# CPS.net
KiCad netlist of a schematic drawn in Altium Designer
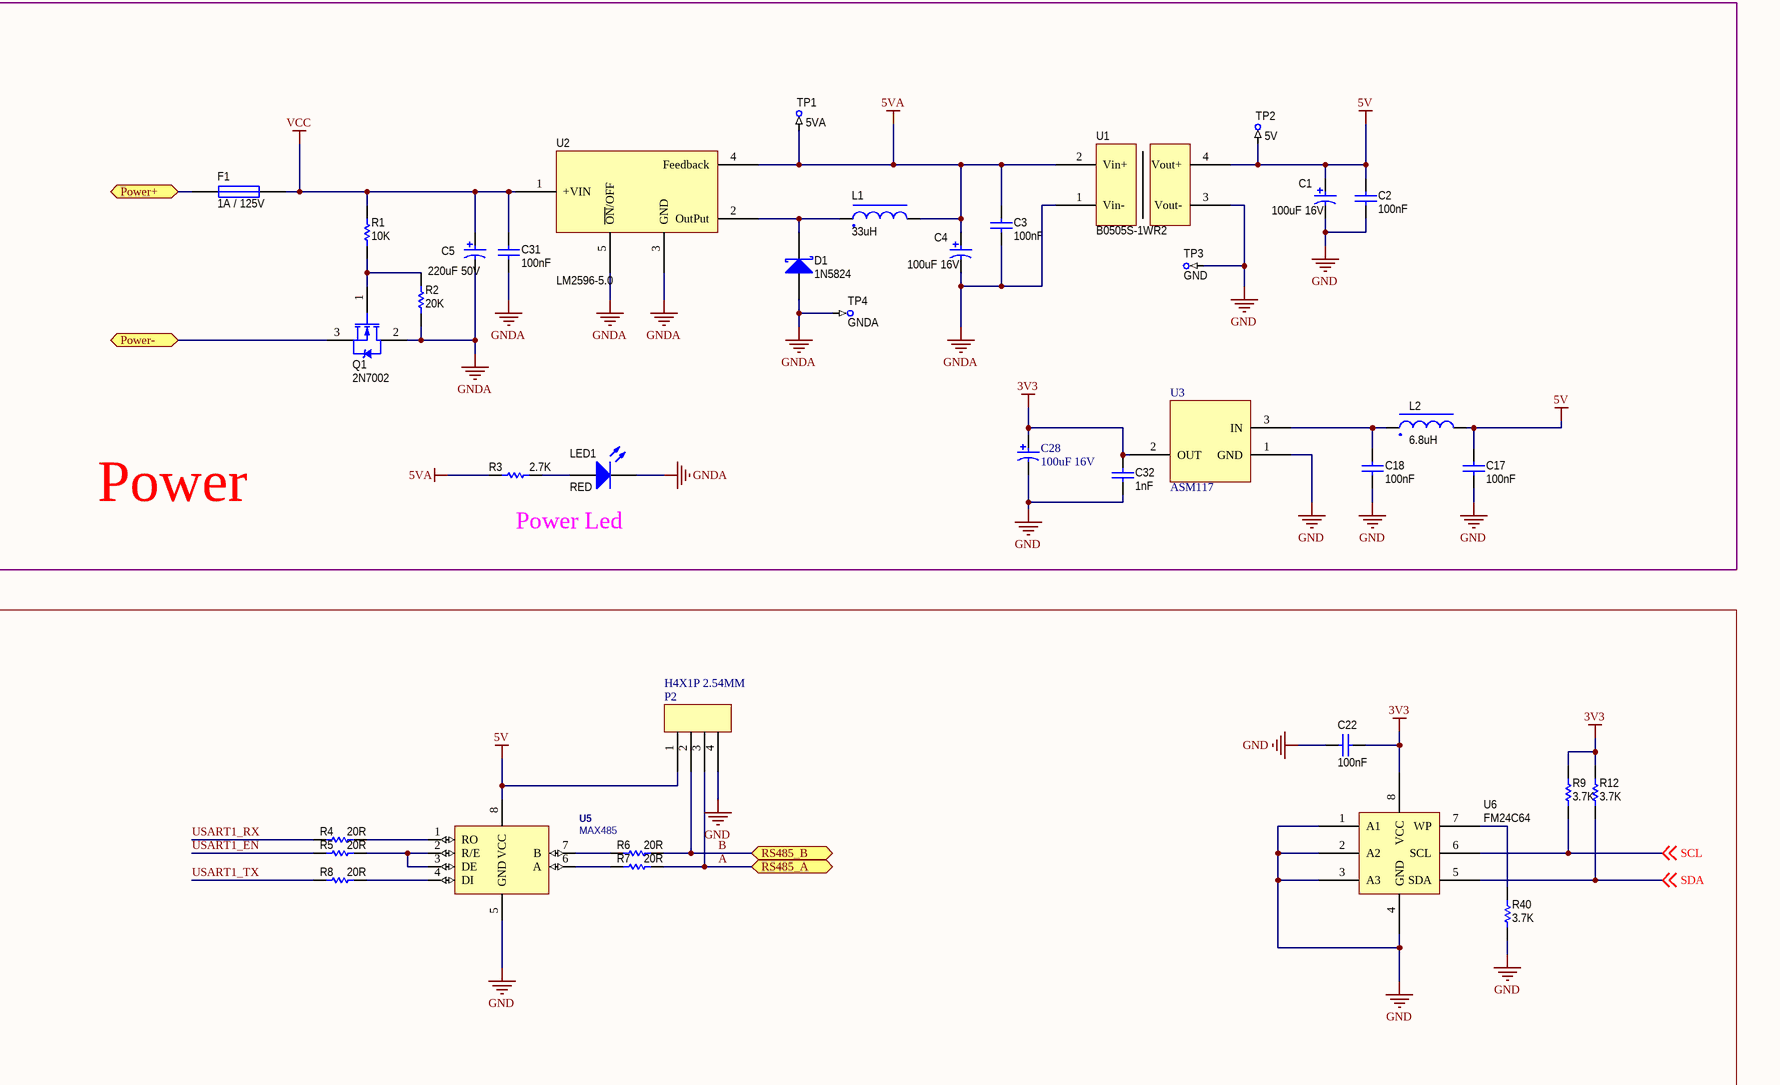
[diagram p0: CPS.SchDoc, top left]
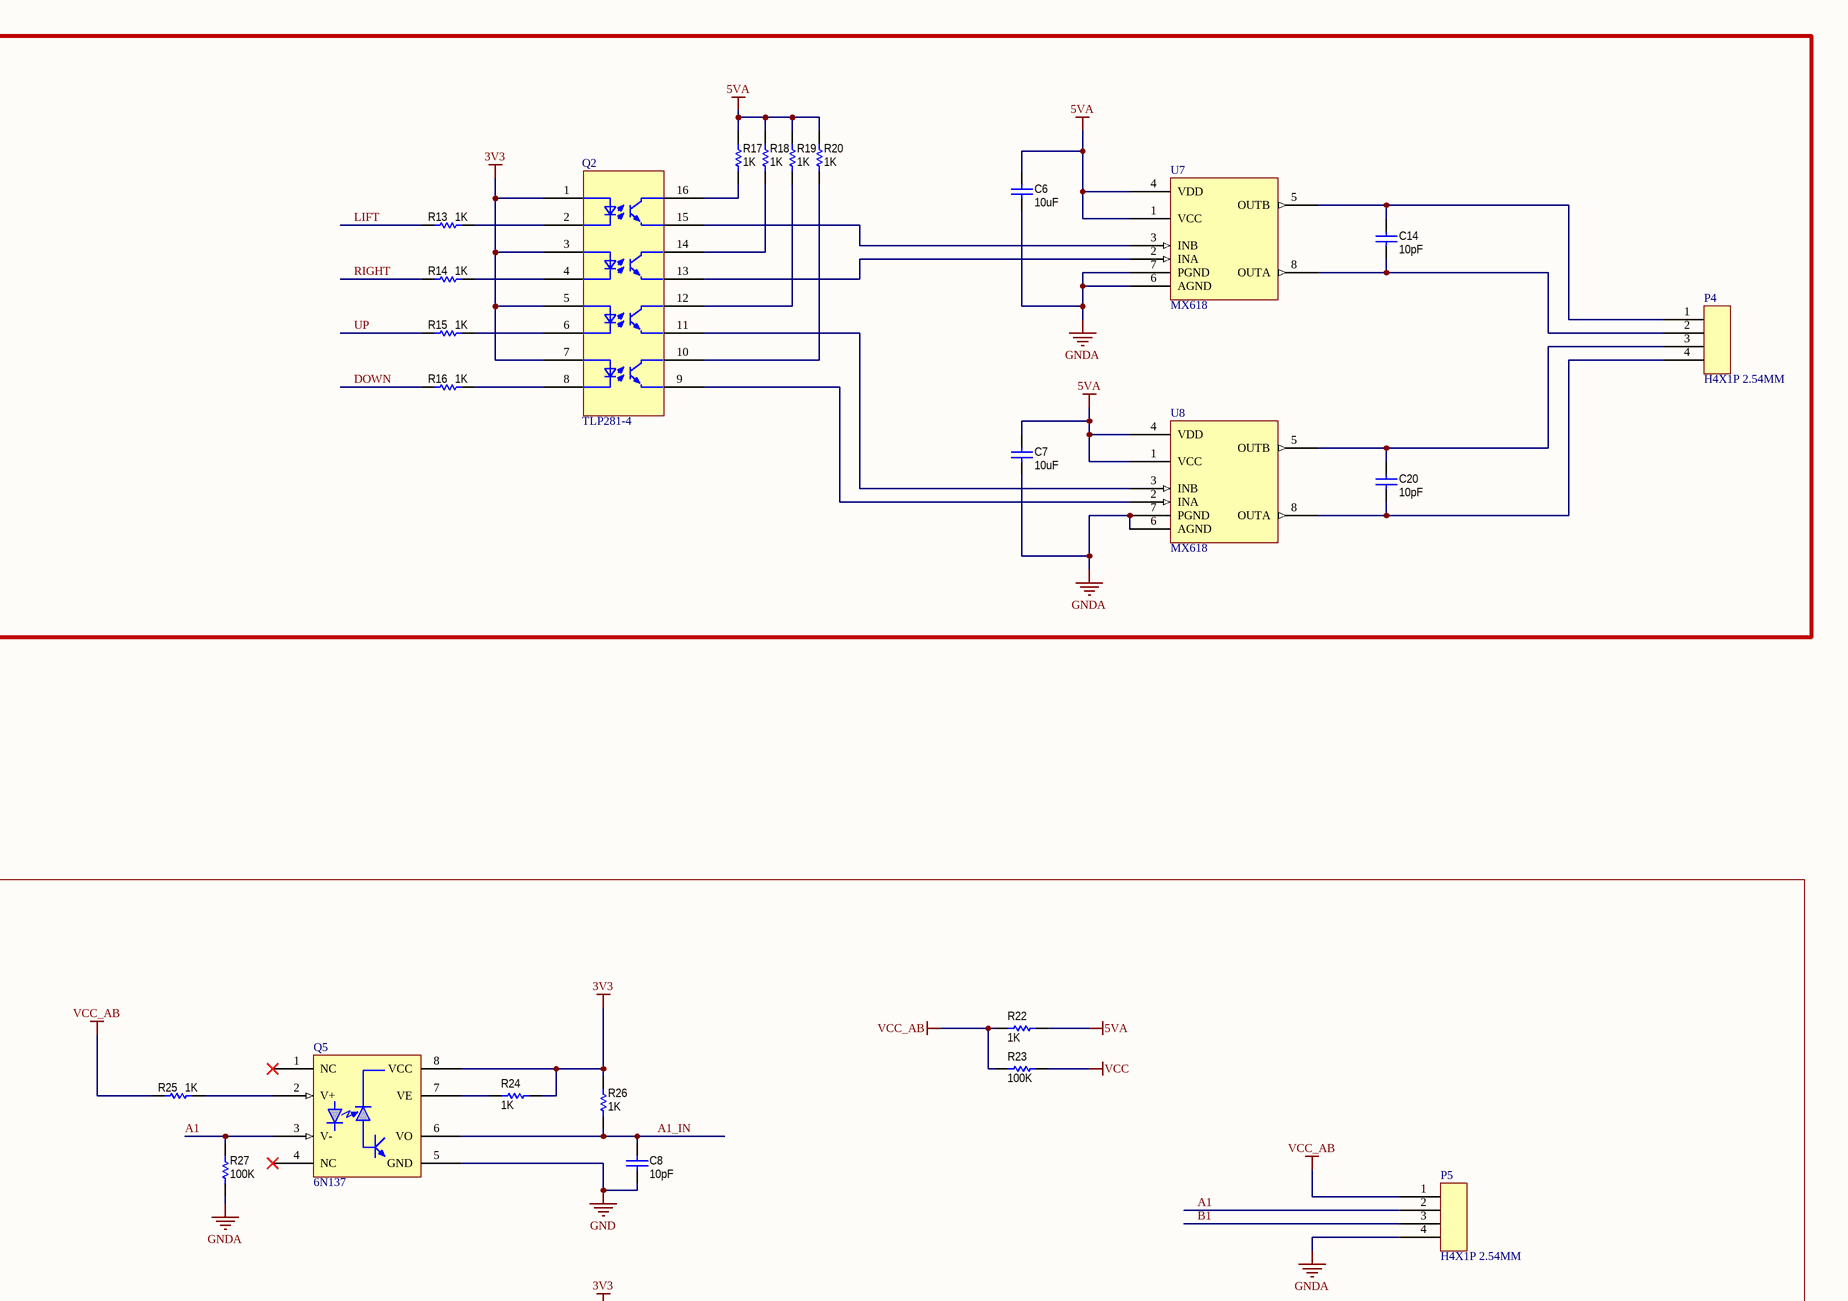
[diagram p1: CPS.SchDoc, top right]
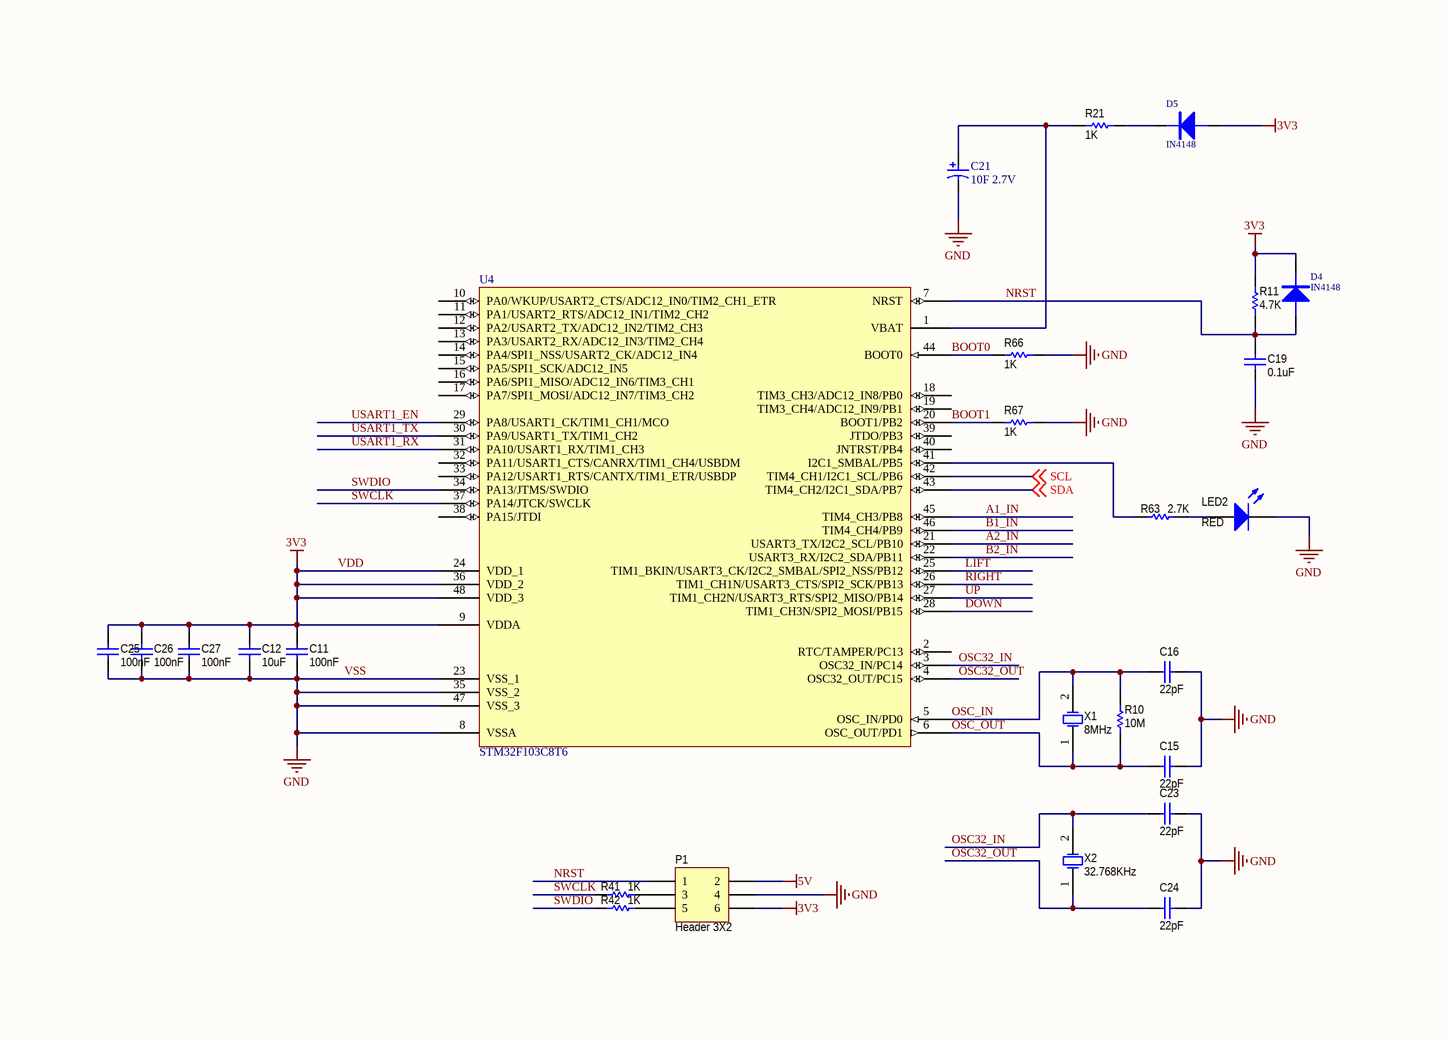
[diagram p2: CPS.SchDoc, bottom left]
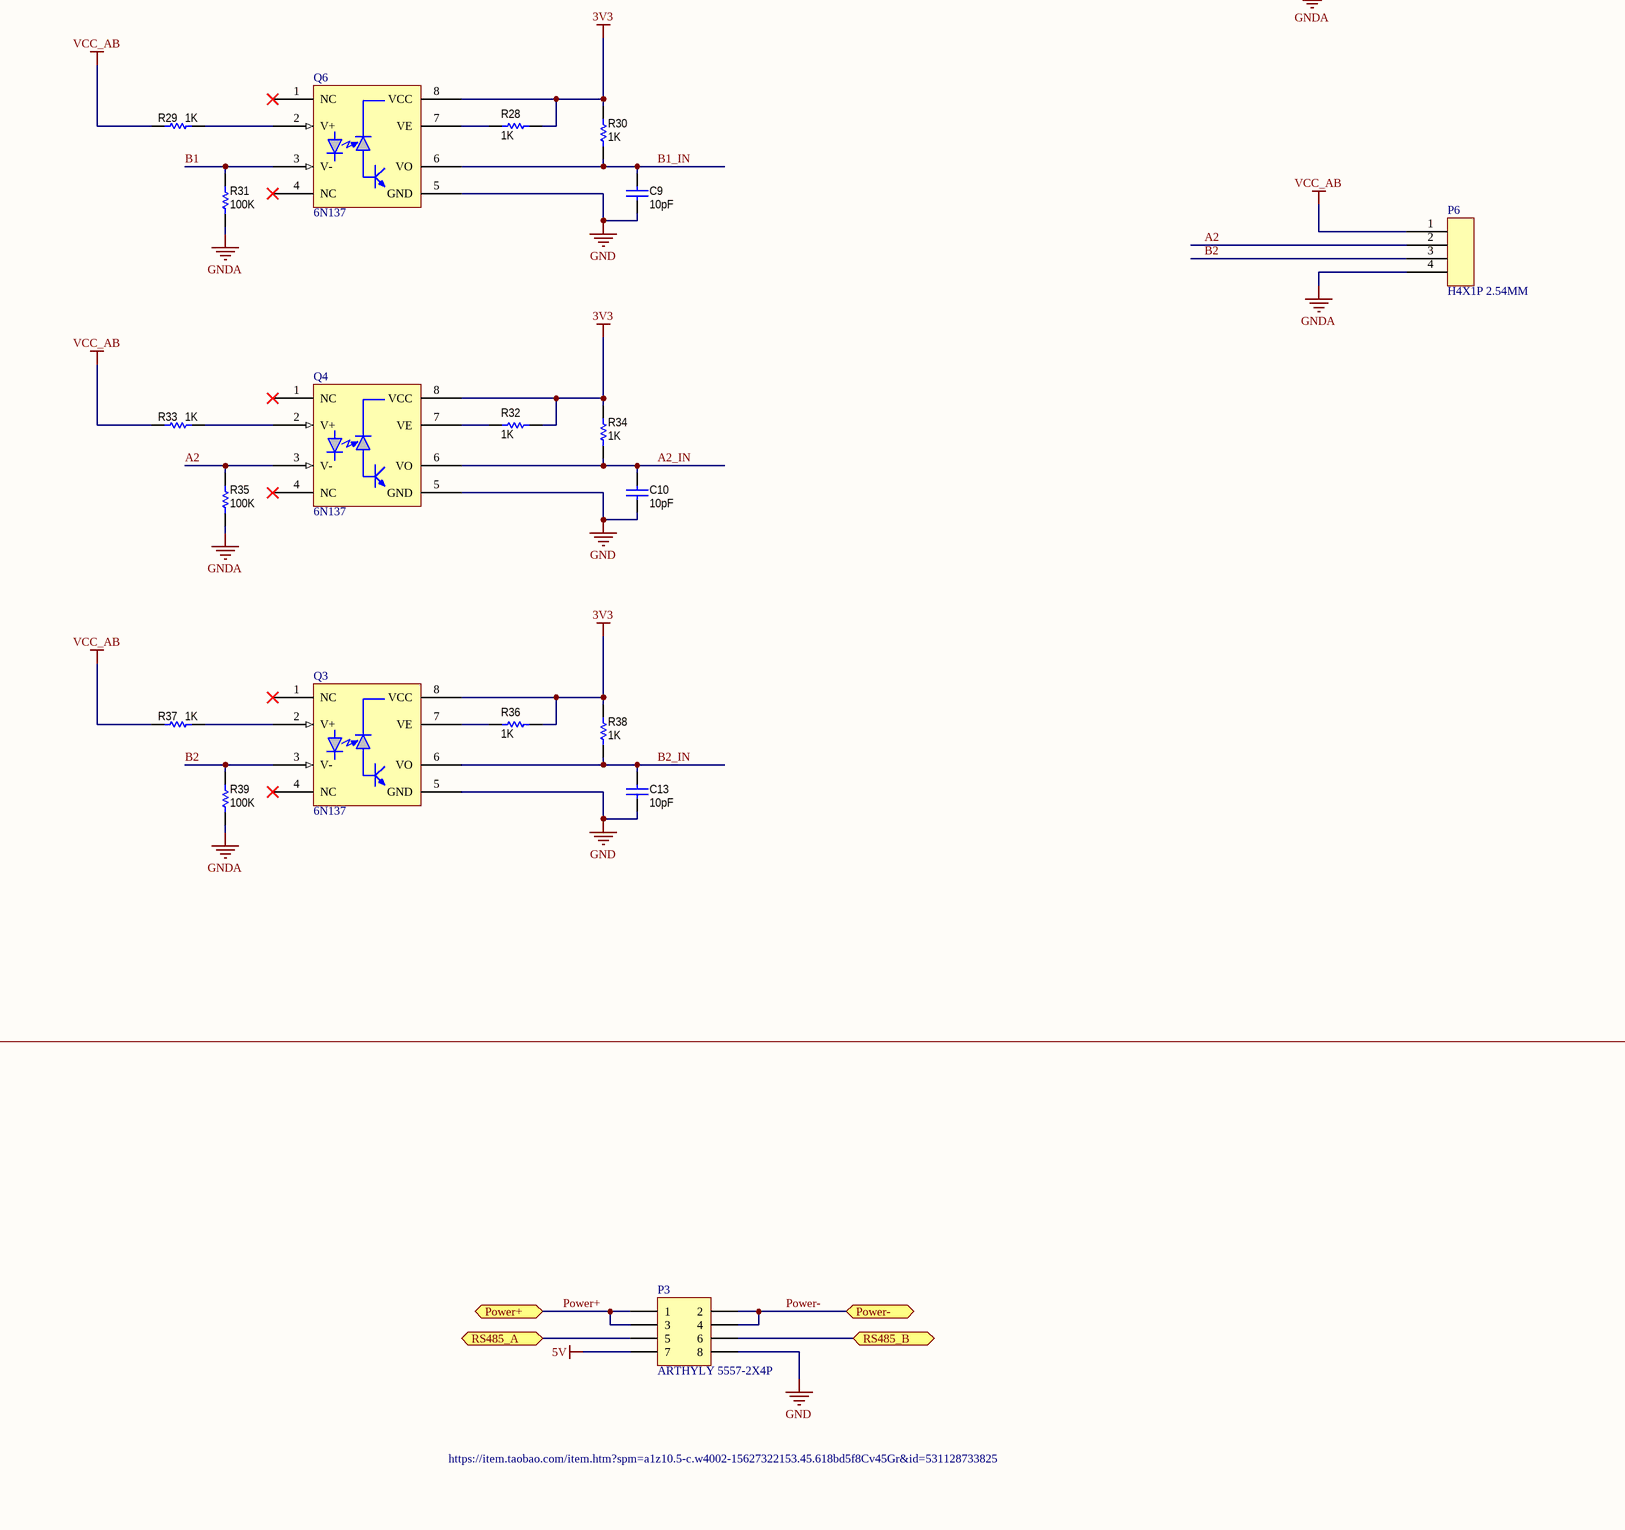
[diagram p3: CPS.SchDoc, bottom right]

(export (version "E")
  (design (tool "Eeschema 10.0.6"))
  (components
    (comp (ref "C1")
      (value "100uF 16V")
      (footprint "SMD-D6.5MM")
      (description "Polar Capacitor")
      (libsource (lib "ZLM") (part "CAP-P"))
    )
    (comp (ref "C2")
      (value "100nF")
      (footprint "0603S")
      (description "Capacitor")
      (libsource (lib "ZLM") (part "CAP-NP"))
    )
    (comp (ref "C3")
      (value "100nF")
      (footprint "0603S")
      (description "Capacitor")
      (libsource (lib "ZLM") (part "CAP-NP"))
    )
    (comp (ref "C4")
      (value "100uF 16V")
      (footprint "SMD-D6.5MM")
      (description "Polar Capacitor")
      (libsource (lib "ZLM") (part "CAP-P"))
    )
    (comp (ref "C5")
      (value "220uF 50V")
      (footprint "SMD-D10MM")
      (description "Polar Capacitor")
      (libsource (lib "ZLM") (part "CAP-P"))
    )
    (comp (ref "C6")
      (value "10uF")
      (footprint "1210S")
      (description "Capacitor")
      (libsource (lib "ZLM") (part "CAP-NP"))
    )
    (comp (ref "C7")
      (value "10uF")
      (footprint "1210S")
      (description "Capacitor")
      (libsource (lib "ZLM") (part "CAP-NP"))
    )
    (comp (ref "C8")
      (value "10pF")
      (footprint "0805S")
      (description "Capacitor")
      (libsource (lib "ZLM") (part "CAP-NP"))
    )
    (comp (ref "C9")
      (value "10pF")
      (footprint "0805S")
      (description "Capacitor")
      (libsource (lib "ZLM") (part "CAP-NP"))
    )
    (comp (ref "C10")
      (value "10pF")
      (footprint "0805S")
      (description "Capacitor")
      (libsource (lib "ZLM") (part "CAP-NP"))
    )
    (comp (ref "C11")
      (value "100nF")
      (footprint "0603S")
      (description "Capacitor")
      (libsource (lib "ZLM") (part "CAP-NP"))
    )
    (comp (ref "C12")
      (value "10uF")
      (footprint "1210S")
      (description "Capacitor")
      (libsource (lib "ZLM") (part "CAP-NP"))
    )
    (comp (ref "C13")
      (value "10pF")
      (footprint "0805S")
      (description "Capacitor")
      (libsource (lib "ZLM") (part "CAP-NP"))
    )
    (comp (ref "C14")
      (value "10pF")
      (footprint "0805S")
      (description "Capacitor")
      (libsource (lib "ZLM") (part "CAP-NP"))
    )
    (comp (ref "C15")
      (value "22pF")
      (footprint "0603S")
      (description "Capacitor")
      (libsource (lib "ZLM") (part "CAP-NP"))
    )
    (comp (ref "C16")
      (value "22pF")
      (footprint "0603S")
      (description "Capacitor")
      (libsource (lib "ZLM") (part "CAP-NP"))
    )
    (comp (ref "C17")
      (value "100nF")
      (footprint "0805S")
      (description "Capacitor")
      (libsource (lib "ZLM") (part "CAP-NP"))
    )
    (comp (ref "C18")
      (value "100nF")
      (footprint "0805S")
      (description "Capacitor")
      (libsource (lib "ZLM") (part "CAP-NP"))
    )
    (comp (ref "C19")
      (value "0.1uF")
      (footprint "0603S")
      (description "Capacitor")
      (libsource (lib "ZLM") (part "CAP-NP"))
    )
    (comp (ref "C20")
      (value "10pF")
      (footprint "0805S")
      (description "Capacitor")
      (libsource (lib "ZLM") (part "CAP-NP"))
    )
    (comp (ref "C21")
      (value "10F 2.7V")
      (footprint "DIP2_90_31MM")
      (description "Polar Capacitor")
      (libsource (lib "ZLM") (part "CAP-P"))
    )
    (comp (ref "C22")
      (value "100nF")
      (footprint "0805S")
      (description "Capacitor")
      (libsource (lib "ZLM") (part "CAP-NP"))
    )
    (comp (ref "C23")
      (value "22pF")
      (footprint "0603S")
      (description "Capacitor")
      (libsource (lib "ZLM") (part "CAP-NP"))
    )
    (comp (ref "C24")
      (value "22pF")
      (footprint "0603S")
      (description "Capacitor")
      (libsource (lib "ZLM") (part "CAP-NP"))
    )
    (comp (ref "C25")
      (value "100nF")
      (footprint "0603S")
      (description "Capacitor")
      (libsource (lib "ZLM") (part "CAP-NP"))
    )
    (comp (ref "C26")
      (value "100nF")
      (footprint "0603S")
      (description "Capacitor")
      (libsource (lib "ZLM") (part "CAP-NP"))
    )
    (comp (ref "C27")
      (value "100nF")
      (footprint "0603S")
      (description "Capacitor")
      (libsource (lib "ZLM") (part "CAP-NP"))
    )
    (comp (ref "C28")
      (value "100uF 16V")
      (footprint "SMD-D6.5MM")
      (description "Polar Capacitor")
      (libsource (lib "ZLM") (part "CAP-P"))
    )
    (comp (ref "C31")
      (value "100nF")
      (footprint "0805S")
      (description "Capacitor")
      (libsource (lib "ZLM") (part "CAP-NP"))
    )
    (comp (ref "C32")
      (value "1nF")
      (footprint "0603S")
      (description "Capacitor")
      (libsource (lib "ZLM") (part "CAP-NP"))
    )
    (comp (ref "D1")
      (value "1N5824")
      (footprint "DO-214AC")
      (description "Schottky Barrier Double Diode")
      (libsource (lib "ZLM") (part "DIO-SCHOTTKY-1S-SOT23"))
    )
    (comp (ref "D4")
      (value "IN4148")
      (footprint "1206D")
      (description "Silicon Epitaxial Planar Switching Diode,75V")
      (libsource (lib "ZLM") (part "DIO_SWITCH"))
    )
    (comp (ref "D5")
      (value "IN4148")
      (footprint "1206D")
      (description "Silicon Epitaxial Planar Switching Diode,75V")
      (libsource (lib "ZLM") (part "DIO_SWITCH"))
    )
    (comp (ref "F1")
      (value "1A / 125V")
      (footprint "1810S")
      (description "Fuse")
      (fields (field (name "PUBLISHER") "Altium Limited"))
      (libsource (lib "Miscellaneous Devices") (part "Fuse 1"))
    )
    (comp (ref "L1")
      (value "33uH")
      (footprint "SMD12X12X7")
      (description "Inductor_1")
      (libsource (lib "ZLM") (part "Inductor_1"))
    )
    (comp (ref "L2")
      (value "6.8uH")
      (footprint "0805S")
      (description "Inductor_1")
      (libsource (lib "ZLM") (part "Inductor_1"))
    )
    (comp (ref "LED1")
      (value "RED")
      (footprint "0805SN")
      (description "Typical GREEN SMD LED Agilent make")
      (libsource (lib "ZLM") (part "DIO-LED-1S"))
    )
    (comp (ref "LED2")
      (value "RED")
      (footprint "0805SN")
      (description "Typical GREEN SMD LED Agilent make")
      (libsource (lib "ZLM") (part "DIO-LED-1S"))
    )
    (comp (ref "P1")
      (value "Header 3X2")
      (footprint "Header3x2")
      (description "Header, 3-Pin, Dual row")
      (fields (field (name "PUBLISHER") "Altium Limited"))
      (libsource (lib "Miscellaneous Connectors") (part "Header 3X2"))
    )
    (comp (ref "P2")
      (value "H4X1P 2.54MM")
      (footprint "HDR1X4H-2.54MM")
      (libsource (lib "") (part "H4X1P_1"))
    )
    (comp (ref "P3")
      (value "ARTHYLY 5557-2X4P")
      (footprint "5557_2X4P")
      (description "Header, 4-Pin, Dual row")
      (fields (field (name "PUBLISHER") "Altium Limited"))
      (libsource (lib "Miscellaneous Connectors") (part "Header 4X2"))
    )
    (comp (ref "P4")
      (value "H4X1P 2.54MM")
      (footprint "HDR1X4H-2.54MM")
      (libsource (lib "ZLM") (part "H4X1P"))
    )
    (comp (ref "P5")
      (value "H4X1P 2.54MM")
      (footprint "HDR1X4H-2.54MM")
      (libsource (lib "ZLM") (part "H4X1P"))
    )
    (comp (ref "P6")
      (value "H4X1P 2.54MM")
      (footprint "HDR1X4H-2.54MM")
      (libsource (lib "ZLM") (part "H4X1P"))
    )
    (comp (ref "Q1")
      (value "2N7002")
      (footprint "TO-253")
      (description "N-Channel MOSFET")
      (libsource (lib "ZLM") (part "NMOS"))
    )
    (comp (ref "Q2")
      (value "TLP281-4")
      (footprint "SOP-16")
      (description "TLP281-4 TOSHIBA PHOTOCOUPLER GaAs IRED & PHOTO-TRANSISTOR")
      (libsource (lib "ZLM") (part "Optocoupler 4Pass"))
    )
    (comp (ref "Q3") (value "6N137") (footprint "DIP8") (libsource (lib "ZLM") (part "6N137")))
    (comp (ref "Q4") (value "6N137") (footprint "DIP8") (libsource (lib "ZLM") (part "6N137")))
    (comp (ref "Q5") (value "6N137") (footprint "DIP8") (libsource (lib "ZLM") (part "6N137")))
    (comp (ref "Q6") (value "6N137") (footprint "DIP8") (libsource (lib "ZLM") (part "6N137")))
    (comp (ref "R1")
      (value "10K")
      (footprint "0603S")
      (description "Resistor")
      (libsource (lib "ZLM") (part "RES"))
    )
    (comp (ref "R2")
      (value "20K")
      (footprint "0603S")
      (description "Resistor")
      (libsource (lib "ZLM") (part "RES"))
    )
    (comp (ref "R3")
      (value "2.7K")
      (footprint "0603S")
      (description "Resistor")
      (libsource (lib "ZLM") (part "RES"))
    )
    (comp (ref "R4")
      (value "20R")
      (footprint "0603S")
      (description "Resistor")
      (libsource (lib "ZLM") (part "RES"))
    )
    (comp (ref "R5")
      (value "20R")
      (footprint "0603S")
      (description "Resistor")
      (libsource (lib "ZLM") (part "RES"))
    )
    (comp (ref "R6")
      (value "20R")
      (footprint "0603S")
      (description "Resistor")
      (libsource (lib "ZLM") (part "RES"))
    )
    (comp (ref "R7")
      (value "20R")
      (footprint "0603S")
      (description "Resistor")
      (libsource (lib "ZLM") (part "RES"))
    )
    (comp (ref "R8")
      (value "20R")
      (footprint "0603S")
      (description "Resistor")
      (libsource (lib "ZLM") (part "RES"))
    )
    (comp (ref "R9")
      (value "3.7K")
      (footprint "0603S")
      (description "Resistor")
      (libsource (lib "ZLM") (part "RES"))
    )
    (comp (ref "R10")
      (value "10M")
      (footprint "0603S")
      (description "Resistor")
      (libsource (lib "ZLM") (part "RES"))
    )
    (comp (ref "R11")
      (value "4.7K")
      (footprint "0603S")
      (description "Resistor")
      (libsource (lib "ZLM") (part "RES"))
    )
    (comp (ref "R12")
      (value "3.7K")
      (footprint "0603S")
      (description "Resistor")
      (libsource (lib "ZLM") (part "RES"))
    )
    (comp (ref "R13")
      (value "1K")
      (footprint "0603S")
      (description "Resistor")
      (libsource (lib "ZLM") (part "RES"))
    )
    (comp (ref "R14")
      (value "1K")
      (footprint "0603S")
      (description "Resistor")
      (libsource (lib "ZLM") (part "RES"))
    )
    (comp (ref "R15")
      (value "1K")
      (footprint "0603S")
      (description "Resistor")
      (libsource (lib "ZLM") (part "RES"))
    )
    (comp (ref "R16")
      (value "1K")
      (footprint "0603S")
      (description "Resistor")
      (libsource (lib "ZLM") (part "RES"))
    )
    (comp (ref "R17")
      (value "1K")
      (footprint "0603S")
      (description "Resistor")
      (libsource (lib "ZLM") (part "RES"))
    )
    (comp (ref "R18")
      (value "1K")
      (footprint "0603S")
      (description "Resistor")
      (libsource (lib "ZLM") (part "RES"))
    )
    (comp (ref "R19")
      (value "1K")
      (footprint "0603S")
      (description "Resistor")
      (libsource (lib "ZLM") (part "RES"))
    )
    (comp (ref "R20")
      (value "1K")
      (footprint "0603S")
      (description "Resistor")
      (libsource (lib "ZLM") (part "RES"))
    )
    (comp (ref "R21")
      (value "1K")
      (footprint "1206R")
      (description "Resistor")
      (libsource (lib "ZLM") (part "RES"))
    )
    (comp (ref "R22")
      (value "1K")
      (footprint "1206R")
      (description "Resistor")
      (libsource (lib "ZLM") (part "RES"))
    )
    (comp (ref "R23")
      (value "100K")
      (footprint "1206R")
      (description "Resistor")
      (libsource (lib "ZLM") (part "RES"))
    )
    (comp (ref "R24")
      (value "1K")
      (footprint "0603S")
      (description "Resistor")
      (libsource (lib "ZLM") (part "RES"))
    )
    (comp (ref "R25")
      (value "1K")
      (footprint "0603S")
      (description "Resistor")
      (libsource (lib "ZLM") (part "RES"))
    )
    (comp (ref "R26")
      (value "1K")
      (footprint "0603S")
      (description "Resistor")
      (libsource (lib "ZLM") (part "RES"))
    )
    (comp (ref "R27")
      (value "100K")
      (footprint "0603S")
      (description "Resistor")
      (libsource (lib "ZLM") (part "RES"))
    )
    (comp (ref "R28")
      (value "1K")
      (footprint "0603S")
      (description "Resistor")
      (libsource (lib "ZLM") (part "RES"))
    )
    (comp (ref "R29")
      (value "1K")
      (footprint "0603S")
      (description "Resistor")
      (libsource (lib "ZLM") (part "RES"))
    )
    (comp (ref "R30")
      (value "1K")
      (footprint "0603S")
      (description "Resistor")
      (libsource (lib "ZLM") (part "RES"))
    )
    (comp (ref "R31")
      (value "100K")
      (footprint "0603S")
      (description "Resistor")
      (libsource (lib "ZLM") (part "RES"))
    )
    (comp (ref "R32")
      (value "1K")
      (footprint "0603S")
      (description "Resistor")
      (libsource (lib "ZLM") (part "RES"))
    )
    (comp (ref "R33")
      (value "1K")
      (footprint "0603S")
      (description "Resistor")
      (libsource (lib "ZLM") (part "RES"))
    )
    (comp (ref "R34")
      (value "1K")
      (footprint "0603S")
      (description "Resistor")
      (libsource (lib "ZLM") (part "RES"))
    )
    (comp (ref "R35")
      (value "100K")
      (footprint "0603S")
      (description "Resistor")
      (libsource (lib "ZLM") (part "RES"))
    )
    (comp (ref "R36")
      (value "1K")
      (footprint "0603S")
      (description "Resistor")
      (libsource (lib "ZLM") (part "RES"))
    )
    (comp (ref "R37")
      (value "1K")
      (footprint "0603S")
      (description "Resistor")
      (libsource (lib "ZLM") (part "RES"))
    )
    (comp (ref "R38")
      (value "1K")
      (footprint "0603S")
      (description "Resistor")
      (libsource (lib "ZLM") (part "RES"))
    )
    (comp (ref "R39")
      (value "100K")
      (footprint "0603S")
      (description "Resistor")
      (libsource (lib "ZLM") (part "RES"))
    )
    (comp (ref "R40")
      (value "3.7K")
      (footprint "0603S")
      (description "Resistor")
      (libsource (lib "ZLM") (part "RES"))
    )
    (comp (ref "R41")
      (value "1K")
      (footprint "0603S")
      (description "Resistor")
      (libsource (lib "ZLM") (part "RES"))
    )
    (comp (ref "R42")
      (value "1K")
      (footprint "0603S")
      (description "Resistor")
      (libsource (lib "ZLM") (part "RES"))
    )
    (comp (ref "R63")
      (value "2.7K")
      (footprint "0603S")
      (description "Resistor")
      (libsource (lib "ZLM") (part "RES"))
    )
    (comp (ref "R66")
      (value "1K")
      (footprint "0603S")
      (description "Resistor")
      (libsource (lib "ZLM") (part "RES"))
    )
    (comp (ref "R67")
      (value "1K")
      (footprint "0603S")
      (description "Resistor")
      (libsource (lib "ZLM") (part "RES"))
    )
    (comp (ref "TP1") (value "5VA") (footprint "T60") (libsource (lib "ZLM") (part "TestPin")))
    (comp (ref "TP2") (value "5V") (footprint "T60") (libsource (lib "ZLM") (part "TestPin")))
    (comp (ref "TP3") (value "GND") (footprint "T60") (libsource (lib "ZLM") (part "TestPin")))
    (comp (ref "TP4") (value "GNDA") (footprint "T60") (libsource (lib "ZLM") (part "TestPin")))
    (comp (ref "U1")
      (value "B0505S-1WR2")
      (footprint "DC/DC 2.54-4P")
      (description "MORNSUN DC/DC")
      (libsource (lib "ZLM") (part "DC/DC"))
    )
    (comp (ref "U2")
      (value "LM2596-5.0")
      (footprint "SOT-263-5")
      (description "LM2596 SIMPLE SWITCHER? Power Converter 150-kHz  3-A Step-Down Voltage Regulator")
      (libsource (lib "ZLM") (part "LM2596-5.0"))
    )
    (comp (ref "U3") (value "ASM117") (footprint "SOT-223") (libsource (lib "ASM117") (part "ASM117")))
    (comp (ref "U4")
      (value "STM32F103C8T6")
      (footprint "LQFP-48")
      (description "ST MCU,STM32F103C8T6,64Kb Flash,20Kb RAM")
      (libsource (lib "ZLM") (part "STM32F103C8T6"))
    )
    (comp (ref "U5")
      (value "MAX485")
      (footprint "SOP-8")
      (description "MAXIM,RS-485/RS-422 Transceivers")
      (libsource (lib "ZLM") (part "RS485"))
    )
    (comp (ref "U6")
      (value "FM24C64")
      (footprint "SOP-8")
      (description "FM24C64,8K FLASH,IIC")
      (libsource (lib "ZLM") (part "F24CXX"))
    )
    (comp (ref "U7")
      (value "MX618")
      (footprint "SOP-8")
      (description "DC 2V-9.6V Motor Contl")
      (libsource (lib "ZLM") (part "MX618"))
    )
    (comp (ref "U8")
      (value "MX618")
      (footprint "SOP-8")
      (description "DC 2V-9.6V Motor Contl")
      (libsource (lib "ZLM") (part "MX618"))
    )
    (comp (ref "X1")
      (value "8MHz")
      (footprint "5032")
      (description "Crystal Oscillator")
      (fields (field (name "PUBLISHER") "Altium Limited"))
      (libsource (lib "ZLM") (part "XTAL"))
    )
    (comp (ref "X2")
      (value "32.768KHz")
      (footprint "0805S")
      (description "Crystal Oscillator")
      (fields (field (name "PUBLISHER") "Altium Limited"))
      (libsource (lib "ZLM") (part "XTAL"))
    )
  )
  (nets
    (net (code "1") (name "/A") (class "Default")
      (node (ref "P2") (pin "3") (pinfunction "3_3") (pintype "passive"))
      (node (ref "P3") (pin "5") (pinfunction "5_5") (pintype "passive"))
      (node (ref "R7") (pin "2") (pinfunction "2_2") (pintype "passive"))
    )
    (net (code "2") (name "/A1") (class "Default")
      (node (ref "P5") (pin "2") (pinfunction "2_2") (pintype "passive"))
      (node (ref "Q5") (pin "3") (pinfunction "V-_3") (pintype "input"))
      (node (ref "R27") (pin "1") (pinfunction "1_1") (pintype "passive"))
    )
    (net (code "3") (name "/A1_IN") (class "Default")
      (node (ref "C8") (pin "2") (pinfunction "2_2") (pintype "passive"))
      (node (ref "Q5") (pin "6") (pinfunction "VO_6") (pintype "passive"))
      (node (ref "R26") (pin "2") (pinfunction "2_2") (pintype "passive"))
      (node (ref "U4") (pin "45") (pinfunction "TIM4_CH3/PB8_45") (pintype "bidirectional"))
    )
    (net (code "4") (name "/A2") (class "Default")
      (node (ref "P6") (pin "2") (pinfunction "2_2") (pintype "passive"))
      (node (ref "Q4") (pin "3") (pinfunction "V-_3") (pintype "input"))
      (node (ref "R35") (pin "1") (pinfunction "1_1") (pintype "passive"))
    )
    (net (code "5") (name "/A2_IN") (class "Default")
      (node (ref "C10") (pin "2") (pinfunction "2_2") (pintype "passive"))
      (node (ref "Q4") (pin "6") (pinfunction "VO_6") (pintype "passive"))
      (node (ref "R34") (pin "2") (pinfunction "2_2") (pintype "passive"))
      (node (ref "U4") (pin "21") (pinfunction "USART3_TX/I2C2_SCL/PB10_21") (pintype "bidirectional"))
    )
    (net (code "6") (name "/B") (class "Default")
      (node (ref "P2") (pin "2") (pinfunction "2_2") (pintype "passive"))
      (node (ref "P3") (pin "6") (pinfunction "6_6") (pintype "passive"))
      (node (ref "R6") (pin "2") (pinfunction "2_2") (pintype "passive"))
    )
    (net (code "7") (name "/B1") (class "Default")
      (node (ref "P5") (pin "3") (pinfunction "3_3") (pintype "passive"))
      (node (ref "Q6") (pin "3") (pinfunction "V-_3") (pintype "input"))
      (node (ref "R31") (pin "1") (pinfunction "1_1") (pintype "passive"))
    )
    (net (code "8") (name "/B1_IN") (class "Default")
      (node (ref "C9") (pin "2") (pinfunction "2_2") (pintype "passive"))
      (node (ref "Q6") (pin "6") (pinfunction "VO_6") (pintype "passive"))
      (node (ref "R30") (pin "2") (pinfunction "2_2") (pintype "passive"))
      (node (ref "U4") (pin "46") (pinfunction "TIM4_CH4/PB9_46") (pintype "bidirectional"))
    )
    (net (code "9") (name "/B2") (class "Default")
      (node (ref "P6") (pin "3") (pinfunction "3_3") (pintype "passive"))
      (node (ref "Q3") (pin "3") (pinfunction "V-_3") (pintype "input"))
      (node (ref "R39") (pin "1") (pinfunction "1_1") (pintype "passive"))
    )
    (net (code "10") (name "/B2_IN") (class "Default")
      (node (ref "C13") (pin "2") (pinfunction "2_2") (pintype "passive"))
      (node (ref "Q3") (pin "6") (pinfunction "VO_6") (pintype "passive"))
      (node (ref "R38") (pin "2") (pinfunction "2_2") (pintype "passive"))
      (node (ref "U4") (pin "22") (pinfunction "USART3_RX/I2C2_SDA/PB11_22") (pintype "bidirectional"))
    )
    (net (code "11") (name "/BOOT0") (class "Default")
      (node (ref "R66") (pin "1") (pinfunction "1_1") (pintype "passive"))
      (node (ref "U4") (pin "44") (pinfunction "BOOT0_44") (pintype "input"))
    )
    (net (code "12") (name "/BOOT1") (class "Default")
      (node (ref "R67") (pin "1") (pinfunction "1_1") (pintype "passive"))
      (node (ref "U4") (pin "20") (pinfunction "BOOT1/PB2_20") (pintype "bidirectional"))
    )
    (net (code "13") (name "/DOWN") (class "Default")
      (node (ref "R16") (pin "2") (pinfunction "2_2") (pintype "passive"))
      (node (ref "U4") (pin "28") (pinfunction "TIM1_CH3N/SPI2_MOSI/PB15_28") (pintype "bidirectional"))
    )
    (net (code "14") (name "/LIFT") (class "Default")
      (node (ref "R13") (pin "2") (pinfunction "2_2") (pintype "passive"))
      (node (ref "U4") (pin "25") (pinfunction "TIM1_BKIN/USART3_CK/I2C2_SMBAL/SPI2_NSS/PB12_25") (pintype "bidirectional"))
    )
    (net (code "15") (name "/NRST") (class "Default")
      (node (ref "C19") (pin "2") (pinfunction "2_2") (pintype "passive"))
      (node (ref "D4") (pin "1") (pinfunction "A_1") (pintype "passive"))
      (node (ref "P1") (pin "1") (pinfunction "1_1") (pintype "passive"))
      (node (ref "R11") (pin "2") (pinfunction "2_2") (pintype "passive"))
      (node (ref "U4") (pin "7") (pinfunction "NRST_7") (pintype "bidirectional"))
    )
    (net (code "16") (name "/OSC32_IN") (class "Default")
      (node (ref "C23") (pin "2") (pinfunction "2_2") (pintype "passive"))
      (node (ref "U4") (pin "3") (pinfunction "OSC32_IN/PC14_3") (pintype "bidirectional"))
      (node (ref "X2") (pin "2") (pinfunction "OSC2_2") (pintype "passive"))
    )
    (net (code "17") (name "/OSC32_OUT") (class "Default")
      (node (ref "C24") (pin "2") (pinfunction "2_2") (pintype "passive"))
      (node (ref "U4") (pin "4") (pinfunction "OSC32_OUT/PC15_4") (pintype "bidirectional"))
      (node (ref "X2") (pin "1") (pinfunction "OSC1_1") (pintype "passive"))
    )
    (net (code "18") (name "/OSC_IN") (class "Default")
      (node (ref "C16") (pin "2") (pinfunction "2_2") (pintype "passive"))
      (node (ref "R10") (pin "2") (pinfunction "2_2") (pintype "passive"))
      (node (ref "U4") (pin "5") (pinfunction "OSC_IN/PD0_5") (pintype "input"))
      (node (ref "X1") (pin "2") (pinfunction "OSC2_2") (pintype "passive"))
    )
    (net (code "19") (name "/OSC_OUT") (class "Default")
      (node (ref "C15") (pin "2") (pinfunction "2_2") (pintype "passive"))
      (node (ref "R10") (pin "1") (pinfunction "1_1") (pintype "passive"))
      (node (ref "U4") (pin "6") (pinfunction "OSC_OUT/PD1_6") (pintype "output"))
      (node (ref "X1") (pin "1") (pinfunction "OSC1_1") (pintype "passive"))
    )
    (net (code "20") (name "/Power+") (class "Default")
      (node (ref "F1") (pin "1") (pinfunction "1_1") (pintype "passive"))
      (node (ref "P3") (pin "1") (pinfunction "1_1") (pintype "passive"))
      (node (ref "P3") (pin "3") (pinfunction "3_3") (pintype "passive"))
    )
    (net (code "21") (name "/Power-") (class "Default")
      (node (ref "P3") (pin "2") (pinfunction "2_2") (pintype "passive"))
      (node (ref "P3") (pin "4") (pinfunction "4_4") (pintype "passive"))
      (node (ref "Q1") (pin "3") (pinfunction "D_3") (pintype "passive"))
    )
    (net (code "22") (name "/RIGHT") (class "Default")
      (node (ref "R14") (pin "2") (pinfunction "2_2") (pintype "passive"))
      (node (ref "U4") (pin "26") (pinfunction "TIM1_CH1N/USART3_CTS/SPI2_SCK/PB13_26") (pintype "bidirectional"))
    )
    (net (code "23") (name "/SWCLK") (class "Default")
      (node (ref "R41") (pin "1") (pinfunction "1_1") (pintype "passive"))
      (node (ref "U4") (pin "37") (pinfunction "PA14/JTCK/SWCLK_37") (pintype "bidirectional"))
    )
    (net (code "24") (name "/SWDIO") (class "Default")
      (node (ref "R42") (pin "1") (pinfunction "1_1") (pintype "passive"))
      (node (ref "U4") (pin "34") (pinfunction "PA13/JTMS/SWDIO_34") (pintype "bidirectional"))
    )
    (net (code "25") (name "/UP") (class "Default")
      (node (ref "R15") (pin "2") (pinfunction "2_2") (pintype "passive"))
      (node (ref "U4") (pin "27") (pinfunction "TIM1_CH2N/USART3_RTS/SPI2_MISO/PB14_27") (pintype "bidirectional"))
    )
    (net (code "26") (name "/USART1_EN") (class "Default")
      (node (ref "R5") (pin "1") (pinfunction "1_1") (pintype "passive"))
      (node (ref "U4") (pin "29") (pinfunction "PA8/USART1_CK/TIM1_CH1/MCO_29") (pintype "bidirectional"))
    )
    (net (code "27") (name "/USART1_RX") (class "Default")
      (node (ref "R4") (pin "1") (pinfunction "1_1") (pintype "passive"))
      (node (ref "U4") (pin "31") (pinfunction "PA10/USART1_RX/TIM1_CH3_31") (pintype "bidirectional"))
    )
    (net (code "28") (name "/USART1_TX") (class "Default")
      (node (ref "R8") (pin "1") (pinfunction "1_1") (pintype "passive"))
      (node (ref "U4") (pin "30") (pinfunction "PA9/USART1_TX/TIM1_CH2_30") (pintype "bidirectional"))
    )
    (net (code "29") (name "3V3") (class "Default")
      (node (ref "C11") (pin "2") (pinfunction "2_2") (pintype "passive"))
      (node (ref "C12") (pin "2") (pinfunction "2_2") (pintype "passive"))
      (node (ref "C22") (pin "2") (pinfunction "2_2") (pintype "passive"))
      (node (ref "C25") (pin "2") (pinfunction "2_2") (pintype "passive"))
      (node (ref "C26") (pin "2") (pinfunction "2_2") (pintype "passive"))
      (node (ref "C27") (pin "2") (pinfunction "2_2") (pintype "passive"))
      (node (ref "C28") (pin "1") (pinfunction "1_1") (pintype "passive"))
      (node (ref "C32") (pin "1") (pinfunction "1_1") (pintype "passive"))
      (node (ref "D4") (pin "2") (pinfunction "K_2") (pintype "passive"))
      (node (ref "D5") (pin "1") (pinfunction "A_1") (pintype "passive"))
      (node (ref "P1") (pin "6") (pinfunction "6_6") (pintype "passive"))
      (node (ref "Q2") (pin "1") (pinfunction "1_1") (pintype "passive"))
      (node (ref "Q2") (pin "3") (pinfunction "3_3") (pintype "passive"))
      (node (ref "Q2") (pin "5") (pinfunction "5_5") (pintype "passive"))
      (node (ref "Q2") (pin "7") (pinfunction "7_7") (pintype "passive"))
      (node (ref "Q3") (pin "8") (pinfunction "VCC_8") (pintype "power_in"))
      (node (ref "Q4") (pin "8") (pinfunction "VCC_8") (pintype "power_in"))
      (node (ref "Q5") (pin "8") (pinfunction "VCC_8") (pintype "power_in"))
      (node (ref "Q6") (pin "8") (pinfunction "VCC_8") (pintype "power_in"))
      (node (ref "R11") (pin "1") (pinfunction "1_1") (pintype "passive"))
      (node (ref "R12") (pin "2") (pinfunction "2_2") (pintype "passive"))
      (node (ref "R24") (pin "1") (pinfunction "1_1") (pintype "passive"))
      (node (ref "R26") (pin "1") (pinfunction "1_1") (pintype "passive"))
      (node (ref "R28") (pin "1") (pinfunction "1_1") (pintype "passive"))
      (node (ref "R30") (pin "1") (pinfunction "1_1") (pintype "passive"))
      (node (ref "R32") (pin "1") (pinfunction "1_1") (pintype "passive"))
      (node (ref "R34") (pin "1") (pinfunction "1_1") (pintype "passive"))
      (node (ref "R36") (pin "1") (pinfunction "1_1") (pintype "passive"))
      (node (ref "R38") (pin "1") (pinfunction "1_1") (pintype "passive"))
      (node (ref "R9") (pin "2") (pinfunction "2_2") (pintype "passive"))
      (node (ref "U3") (pin "2") (pinfunction "OUT_2") (pintype "passive"))
      (node (ref "U4") (pin "24") (pinfunction "VDD_1_24") (pintype "power_in"))
      (node (ref "U4") (pin "36") (pinfunction "VDD_2_36") (pintype "power_in"))
      (node (ref "U4") (pin "48") (pinfunction "VDD_3_48") (pintype "power_in"))
      (node (ref "U4") (pin "9") (pinfunction "VDDA_9") (pintype "power_in"))
      (node (ref "U6") (pin "8") (pinfunction "VCC_8") (pintype "passive"))
    )
    (net (code "30") (name "5V") (class "Default")
      (node (ref "C1") (pin "1") (pinfunction "1_1") (pintype "passive"))
      (node (ref "C17") (pin "2") (pinfunction "2_2") (pintype "passive"))
      (node (ref "C2") (pin "1") (pinfunction "1_1") (pintype "passive"))
      (node (ref "L2") (pin "2") (pinfunction "2_2") (pintype "passive"))
      (node (ref "P1") (pin "2") (pinfunction "2_2") (pintype "passive"))
      (node (ref "P2") (pin "1") (pinfunction "1_1") (pintype "passive"))
      (node (ref "P3") (pin "7") (pinfunction "7_7") (pintype "passive"))
      (node (ref "TP2") (pin "1") (pinfunction "1_1") (pintype "input"))
      (node (ref "U1") (pin "4") (pinfunction "Vout+_4") (pintype "passive"))
      (node (ref "U5") (pin "8") (pinfunction "VCC_8") (pintype "power_in"))
    )
    (net (code "31") (name "5VA") (class "Default")
      (node (ref "C3") (pin "1") (pinfunction "1_1") (pintype "passive"))
      (node (ref "C4") (pin "1") (pinfunction "1_1") (pintype "passive"))
      (node (ref "C6") (pin "2") (pinfunction "2_2") (pintype "passive"))
      (node (ref "C7") (pin "2") (pinfunction "2_2") (pintype "passive"))
      (node (ref "L1") (pin "2") (pinfunction "2_2") (pintype "passive"))
      (node (ref "R17") (pin "1") (pinfunction "1_1") (pintype "passive"))
      (node (ref "R18") (pin "1") (pinfunction "1_1") (pintype "passive"))
      (node (ref "R19") (pin "1") (pinfunction "1_1") (pintype "passive"))
      (node (ref "R20") (pin "1") (pinfunction "1_1") (pintype "passive"))
      (node (ref "R22") (pin "2") (pinfunction "2_2") (pintype "passive"))
      (node (ref "R3") (pin "1") (pinfunction "1_1") (pintype "passive"))
      (node (ref "TP1") (pin "1") (pinfunction "1_1") (pintype "input"))
      (node (ref "U1") (pin "2") (pinfunction "Vin+_2") (pintype "passive"))
      (node (ref "U2") (pin "4") (pinfunction "Feedback_4") (pintype "passive"))
      (node (ref "U7") (pin "1") (pinfunction "VCC_1") (pintype "power_in"))
      (node (ref "U7") (pin "4") (pinfunction "VDD_4") (pintype "power_in"))
      (node (ref "U8") (pin "1") (pinfunction "VCC_1") (pintype "power_in"))
      (node (ref "U8") (pin "4") (pinfunction "VDD_4") (pintype "power_in"))
    )
    (net (code "32") (name "GND") (class "Default")
      (node (ref "C1") (pin "2") (pinfunction "2_2") (pintype "passive"))
      (node (ref "C10") (pin "1") (pinfunction "1_1") (pintype "passive"))
      (node (ref "C11") (pin "1") (pinfunction "1_1") (pintype "passive"))
      (node (ref "C12") (pin "1") (pinfunction "1_1") (pintype "passive"))
      (node (ref "C13") (pin "1") (pinfunction "1_1") (pintype "passive"))
      (node (ref "C15") (pin "1") (pinfunction "1_1") (pintype "passive"))
      (node (ref "C16") (pin "1") (pinfunction "1_1") (pintype "passive"))
      (node (ref "C17") (pin "1") (pinfunction "1_1") (pintype "passive"))
      (node (ref "C18") (pin "1") (pinfunction "1_1") (pintype "passive"))
      (node (ref "C19") (pin "1") (pinfunction "1_1") (pintype "passive"))
      (node (ref "C2") (pin "2") (pinfunction "2_2") (pintype "passive"))
      (node (ref "C21") (pin "2") (pinfunction "2_2") (pintype "passive"))
      (node (ref "C22") (pin "1") (pinfunction "1_1") (pintype "passive"))
      (node (ref "C23") (pin "1") (pinfunction "1_1") (pintype "passive"))
      (node (ref "C24") (pin "1") (pinfunction "1_1") (pintype "passive"))
      (node (ref "C25") (pin "1") (pinfunction "1_1") (pintype "passive"))
      (node (ref "C26") (pin "1") (pinfunction "1_1") (pintype "passive"))
      (node (ref "C27") (pin "1") (pinfunction "1_1") (pintype "passive"))
      (node (ref "C28") (pin "2") (pinfunction "2_2") (pintype "passive"))
      (node (ref "C32") (pin "2") (pinfunction "2_2") (pintype "passive"))
      (node (ref "C8") (pin "1") (pinfunction "1_1") (pintype "passive"))
      (node (ref "C9") (pin "1") (pinfunction "1_1") (pintype "passive"))
      (node (ref "LED2") (pin "2") (pinfunction "K_2") (pintype "passive"))
      (node (ref "P1") (pin "4") (pinfunction "4_4") (pintype "passive"))
      (node (ref "P2") (pin "4") (pinfunction "4_4") (pintype "passive"))
      (node (ref "P3") (pin "8") (pinfunction "8_8") (pintype "passive"))
      (node (ref "Q3") (pin "5") (pinfunction "GND_5") (pintype "power_in"))
      (node (ref "Q4") (pin "5") (pinfunction "GND_5") (pintype "power_in"))
      (node (ref "Q5") (pin "5") (pinfunction "GND_5") (pintype "power_in"))
      (node (ref "Q6") (pin "5") (pinfunction "GND_5") (pintype "power_in"))
      (node (ref "R40") (pin "1") (pinfunction "1_1") (pintype "passive"))
      (node (ref "R66") (pin "2") (pinfunction "2_2") (pintype "passive"))
      (node (ref "R67") (pin "2") (pinfunction "2_2") (pintype "passive"))
      (node (ref "TP3") (pin "1") (pinfunction "1_1") (pintype "input"))
      (node (ref "U1") (pin "3") (pinfunction "Vout-_3") (pintype "passive"))
      (node (ref "U3") (pin "1") (pinfunction "GND_1") (pintype "passive"))
      (node (ref "U4") (pin "23") (pinfunction "VSS_1_23") (pintype "power_in"))
      (node (ref "U4") (pin "35") (pinfunction "VSS_2_35") (pintype "power_in"))
      (node (ref "U4") (pin "47") (pinfunction "VSS_3_47") (pintype "power_in"))
      (node (ref "U4") (pin "8") (pinfunction "VSSA_8") (pintype "power_in"))
      (node (ref "U5") (pin "5") (pinfunction "GND_5") (pintype "power_in"))
      (node (ref "U6") (pin "1") (pinfunction "A1_1") (pintype "passive"))
      (node (ref "U6") (pin "2") (pinfunction "A2_2") (pintype "passive"))
      (node (ref "U6") (pin "3") (pinfunction "A3_3") (pintype "passive"))
      (node (ref "U6") (pin "4") (pinfunction "GND_4") (pintype "passive"))
    )
    (net (code "33") (name "GNDA") (class "Default")
      (node (ref "C3") (pin "2") (pinfunction "2_2") (pintype "passive"))
      (node (ref "C31") (pin "2") (pinfunction "2_2") (pintype "passive"))
      (node (ref "C4") (pin "2") (pinfunction "2_2") (pintype "passive"))
      (node (ref "C5") (pin "2") (pinfunction "2_2") (pintype "passive"))
      (node (ref "C6") (pin "1") (pinfunction "1_1") (pintype "passive"))
      (node (ref "C7") (pin "1") (pinfunction "1_1") (pintype "passive"))
      (node (ref "D1") (pin "1") (pinfunction "A_1") (pintype "passive"))
      (node (ref "LED1") (pin "2") (pinfunction "K_2") (pintype "passive"))
      (node (ref "P5") (pin "4") (pinfunction "4_4") (pintype "passive"))
      (node (ref "P6") (pin "4") (pinfunction "4_4") (pintype "passive"))
      (node (ref "Q1") (pin "2") (pinfunction "S_2") (pintype "passive"))
      (node (ref "R2") (pin "2") (pinfunction "2_2") (pintype "passive"))
      (node (ref "R27") (pin "2") (pinfunction "2_2") (pintype "passive"))
      (node (ref "R31") (pin "2") (pinfunction "2_2") (pintype "passive"))
      (node (ref "R35") (pin "2") (pinfunction "2_2") (pintype "passive"))
      (node (ref "R39") (pin "2") (pinfunction "2_2") (pintype "passive"))
      (node (ref "TP4") (pin "1") (pinfunction "1_1") (pintype "input"))
      (node (ref "U1") (pin "1") (pinfunction "Vin-_1") (pintype "passive"))
      (node (ref "U2") (pin "3") (pinfunction "GND_3") (pintype "passive"))
      (node (ref "U2") (pin "5") (pinfunction "~{ON}/OFF_5") (pintype "passive"))
      (node (ref "U7") (pin "6") (pinfunction "AGND_6") (pintype "passive"))
      (node (ref "U7") (pin "7") (pinfunction "PGND_7") (pintype "passive"))
      (node (ref "U8") (pin "6") (pinfunction "AGND_6") (pintype "passive"))
      (node (ref "U8") (pin "7") (pinfunction "PGND_7") (pintype "passive"))
    )
    (net (code "34") (name "Net-(D1-K)") (class "Default")
      (node (ref "D1") (pin "2") (pinfunction "K_2") (pintype "passive"))
      (node (ref "L1") (pin "1") (pinfunction "1_1") (pintype "passive"))
      (node (ref "U2") (pin "2") (pinfunction "OutPut_2") (pintype "passive"))
    )
    (net (code "35") (name "Net-(D5-K)") (class "Default")
      (node (ref "D5") (pin "2") (pinfunction "K_2") (pintype "passive"))
      (node (ref "R21") (pin "2") (pinfunction "2_2") (pintype "passive"))
    )
    (net (code "36") (name "Net-(LED1-A)") (class "Default")
      (node (ref "LED1") (pin "1") (pinfunction "A_1") (pintype "passive"))
      (node (ref "R3") (pin "2") (pinfunction "2_2") (pintype "passive"))
    )
    (net (code "37") (name "Net-(LED2-A)") (class "Default")
      (node (ref "LED2") (pin "1") (pinfunction "A_1") (pintype "passive"))
      (node (ref "R63") (pin "2") (pinfunction "2_2") (pintype "passive"))
    )
    (net (code "38") (name "Net-(P1-Pad3)") (class "Default")
      (node (ref "P1") (pin "3") (pinfunction "3_3") (pintype "passive"))
      (node (ref "R41") (pin "2") (pinfunction "2_2") (pintype "passive"))
    )
    (net (code "39") (name "Net-(P1-Pad5)") (class "Default")
      (node (ref "P1") (pin "5") (pinfunction "5_5") (pintype "passive"))
      (node (ref "R42") (pin "2") (pinfunction "2_2") (pintype "passive"))
    )
    (net (code "40") (name "Net-(Q1-G)") (class "Default")
      (node (ref "Q1") (pin "1") (pinfunction "G_1") (pintype "passive"))
      (node (ref "R1") (pin "1") (pinfunction "1_1") (pintype "passive"))
      (node (ref "R2") (pin "1") (pinfunction "1_1") (pintype "passive"))
    )
    (net (code "41") (name "Net-(Q2-Pad2)") (class "Default")
      (node (ref "Q2") (pin "2") (pinfunction "2_2") (pintype "passive"))
      (node (ref "R13") (pin "1") (pinfunction "1_1") (pintype "passive"))
    )
    (net (code "42") (name "Net-(Q2-Pad4)") (class "Default")
      (node (ref "Q2") (pin "4") (pinfunction "4_4") (pintype "passive"))
      (node (ref "R14") (pin "1") (pinfunction "1_1") (pintype "passive"))
    )
    (net (code "43") (name "Net-(Q2-Pad6)") (class "Default")
      (node (ref "Q2") (pin "6") (pinfunction "6_6") (pintype "passive"))
      (node (ref "R15") (pin "1") (pinfunction "1_1") (pintype "passive"))
    )
    (net (code "44") (name "Net-(Q2-Pad8)") (class "Default")
      (node (ref "Q2") (pin "8") (pinfunction "8_8") (pintype "passive"))
      (node (ref "R16") (pin "1") (pinfunction "1_1") (pintype "passive"))
    )
    (net (code "45") (name "Net-(Q2-Pad10)") (class "Default")
      (node (ref "Q2") (pin "10") (pinfunction "10_10") (pintype "passive"))
      (node (ref "R20") (pin "2") (pinfunction "2_2") (pintype "passive"))
    )
    (net (code "46") (name "Net-(Q2-Pad12)") (class "Default")
      (node (ref "Q2") (pin "12") (pinfunction "12_12") (pintype "passive"))
      (node (ref "R19") (pin "2") (pinfunction "2_2") (pintype "passive"))
    )
    (net (code "47") (name "Net-(Q2-Pad14)") (class "Default")
      (node (ref "Q2") (pin "14") (pinfunction "14_14") (pintype "passive"))
      (node (ref "R18") (pin "2") (pinfunction "2_2") (pintype "passive"))
    )
    (net (code "48") (name "Net-(Q2-Pad16)") (class "Default")
      (node (ref "Q2") (pin "16") (pinfunction "16_16") (pintype "passive"))
      (node (ref "R17") (pin "2") (pinfunction "2_2") (pintype "passive"))
    )
    (net (code "49") (name "Net-(Q3-V+)") (class "Default")
      (node (ref "Q3") (pin "2") (pinfunction "V+_2") (pintype "input"))
      (node (ref "R37") (pin "1") (pinfunction "1_1") (pintype "passive"))
    )
    (net (code "50") (name "Net-(Q3-VE)") (class "Default")
      (node (ref "Q3") (pin "7") (pinfunction "VE_7") (pintype "passive"))
      (node (ref "R36") (pin "2") (pinfunction "2_2") (pintype "passive"))
    )
    (net (code "51") (name "Net-(Q4-V+)") (class "Default")
      (node (ref "Q4") (pin "2") (pinfunction "V+_2") (pintype "input"))
      (node (ref "R33") (pin "1") (pinfunction "1_1") (pintype "passive"))
    )
    (net (code "52") (name "Net-(Q4-VE)") (class "Default")
      (node (ref "Q4") (pin "7") (pinfunction "VE_7") (pintype "passive"))
      (node (ref "R32") (pin "2") (pinfunction "2_2") (pintype "passive"))
    )
    (net (code "53") (name "Net-(Q5-V+)") (class "Default")
      (node (ref "Q5") (pin "2") (pinfunction "V+_2") (pintype "input"))
      (node (ref "R25") (pin "1") (pinfunction "1_1") (pintype "passive"))
    )
    (net (code "54") (name "Net-(Q5-VE)") (class "Default")
      (node (ref "Q5") (pin "7") (pinfunction "VE_7") (pintype "passive"))
      (node (ref "R24") (pin "2") (pinfunction "2_2") (pintype "passive"))
    )
    (net (code "55") (name "Net-(Q6-V+)") (class "Default")
      (node (ref "Q6") (pin "2") (pinfunction "V+_2") (pintype "input"))
      (node (ref "R29") (pin "1") (pinfunction "1_1") (pintype "passive"))
    )
    (net (code "56") (name "Net-(Q6-VE)") (class "Default")
      (node (ref "Q6") (pin "7") (pinfunction "VE_7") (pintype "passive"))
      (node (ref "R28") (pin "2") (pinfunction "2_2") (pintype "passive"))
    )
    (net (code "57") (name "Net-(U3-IN)") (class "Default")
      (node (ref "C18") (pin "2") (pinfunction "2_2") (pintype "passive"))
      (node (ref "L2") (pin "1") (pinfunction "1_1") (pintype "passive"))
      (node (ref "U3") (pin "3") (pinfunction "IN_3") (pintype "passive"))
    )
    (net (code "58") (name "Net-(U4-I2C1_SMBAL{slash}PB5)") (class "Default")
      (node (ref "R63") (pin "1") (pinfunction "1_1") (pintype "passive"))
      (node (ref "U4") (pin "41") (pinfunction "I2C1_SMBAL/PB5_41") (pintype "bidirectional"))
    )
    (net (code "59") (name "Net-(U4-VBAT)") (class "Default")
      (node (ref "C21") (pin "1") (pinfunction "1_1") (pintype "passive"))
      (node (ref "R21") (pin "1") (pinfunction "1_1") (pintype "passive"))
      (node (ref "U4") (pin "1") (pinfunction "VBAT_1") (pintype "power_in"))
    )
    (net (code "60") (name "Net-(U5-A)") (class "Default")
      (node (ref "R7") (pin "1") (pinfunction "1_1") (pintype "passive"))
      (node (ref "U5") (pin "6") (pinfunction "A_6") (pintype "bidirectional"))
    )
    (net (code "61") (name "Net-(U5-B)") (class "Default")
      (node (ref "R6") (pin "1") (pinfunction "1_1") (pintype "passive"))
      (node (ref "U5") (pin "7") (pinfunction "B_7") (pintype "bidirectional"))
    )
    (net (code "62") (name "Net-(U5-DE)") (class "Default")
      (node (ref "R5") (pin "2") (pinfunction "2_2") (pintype "passive"))
      (node (ref "U5") (pin "2") (pinfunction "R/E_2") (pintype "bidirectional"))
      (node (ref "U5") (pin "3") (pinfunction "DE_3") (pintype "bidirectional"))
    )
    (net (code "63") (name "Net-(U5-DI)") (class "Default")
      (node (ref "R8") (pin "2") (pinfunction "2_2") (pintype "passive"))
      (node (ref "U5") (pin "4") (pinfunction "DI_4") (pintype "bidirectional"))
    )
    (net (code "64") (name "Net-(U5-RO)") (class "Default")
      (node (ref "R4") (pin "2") (pinfunction "2_2") (pintype "passive"))
      (node (ref "U5") (pin "1") (pinfunction "RO_1") (pintype "bidirectional"))
    )
    (net (code "65") (name "Net-(U6-WP)") (class "Default")
      (node (ref "R40") (pin "2") (pinfunction "2_2") (pintype "passive"))
      (node (ref "U6") (pin "7") (pinfunction "WP_7") (pintype "passive"))
    )
    (net (code "66") (name "Net-(U7-INA)") (class "Default")
      (node (ref "Q2") (pin "13") (pinfunction "13_13") (pintype "passive"))
      (node (ref "U7") (pin "2") (pinfunction "INA_2") (pintype "input"))
    )
    (net (code "67") (name "Net-(U7-INB)") (class "Default")
      (node (ref "Q2") (pin "15") (pinfunction "15_15") (pintype "passive"))
      (node (ref "U7") (pin "3") (pinfunction "INB_3") (pintype "input"))
    )
    (net (code "68") (name "Net-(U7-OUTA)") (class "Default")
      (node (ref "C14") (pin "1") (pinfunction "1_1") (pintype "passive"))
      (node (ref "P4") (pin "2") (pinfunction "2_2") (pintype "passive"))
      (node (ref "U7") (pin "8") (pinfunction "OUTA_8") (pintype "output"))
    )
    (net (code "69") (name "Net-(U7-OUTB)") (class "Default")
      (node (ref "C14") (pin "2") (pinfunction "2_2") (pintype "passive"))
      (node (ref "P4") (pin "1") (pinfunction "1_1") (pintype "passive"))
      (node (ref "U7") (pin "5") (pinfunction "OUTB_5") (pintype "output"))
    )
    (net (code "70") (name "Net-(U8-INA)") (class "Default")
      (node (ref "Q2") (pin "9") (pinfunction "9_9") (pintype "passive"))
      (node (ref "U8") (pin "2") (pinfunction "INA_2") (pintype "input"))
    )
    (net (code "71") (name "Net-(U8-INB)") (class "Default")
      (node (ref "Q2") (pin "11") (pinfunction "11_11") (pintype "passive"))
      (node (ref "U8") (pin "3") (pinfunction "INB_3") (pintype "input"))
    )
    (net (code "72") (name "Net-(U8-OUTA)") (class "Default")
      (node (ref "C20") (pin "1") (pinfunction "1_1") (pintype "passive"))
      (node (ref "P4") (pin "4") (pinfunction "4_4") (pintype "passive"))
      (node (ref "U8") (pin "8") (pinfunction "OUTA_8") (pintype "output"))
    )
    (net (code "73") (name "Net-(U8-OUTB)") (class "Default")
      (node (ref "C20") (pin "2") (pinfunction "2_2") (pintype "passive"))
      (node (ref "P4") (pin "3") (pinfunction "3_3") (pintype "passive"))
      (node (ref "U8") (pin "5") (pinfunction "OUTB_5") (pintype "output"))
    )
    (net (code "74") (name "SCL") (class "Default")
      (node (ref "R9") (pin "1") (pinfunction "1_1") (pintype "passive"))
      (node (ref "U4") (pin "42") (pinfunction "TIM4_CH1/I2C1_SCL/PB6_42") (pintype "bidirectional"))
      (node (ref "U6") (pin "6") (pinfunction "SCL_6") (pintype "passive"))
    )
    (net (code "75") (name "SDA") (class "Default")
      (node (ref "R12") (pin "1") (pinfunction "1_1") (pintype "passive"))
      (node (ref "U4") (pin "43") (pinfunction "TIM4_CH2/I2C1_SDA/PB7_43") (pintype "bidirectional"))
      (node (ref "U6") (pin "5") (pinfunction "SDA_5") (pintype "passive"))
    )
    (net (code "76") (name "VCC") (class "Default")
      (node (ref "C31") (pin "1") (pinfunction "1_1") (pintype "passive"))
      (node (ref "C5") (pin "1") (pinfunction "1_1") (pintype "passive"))
      (node (ref "F1") (pin "2") (pinfunction "2_2") (pintype "passive"))
      (node (ref "R1") (pin "2") (pinfunction "2_2") (pintype "passive"))
      (node (ref "R23") (pin "2") (pinfunction "2_2") (pintype "passive"))
      (node (ref "U2") (pin "1") (pinfunction "+VIN_1") (pintype "passive"))
    )
    (net (code "77") (name "VCC_AB") (class "Default")
      (node (ref "P5") (pin "1") (pinfunction "1_1") (pintype "passive"))
      (node (ref "P6") (pin "1") (pinfunction "1_1") (pintype "passive"))
      (node (ref "R22") (pin "1") (pinfunction "1_1") (pintype "passive"))
      (node (ref "R23") (pin "1") (pinfunction "1_1") (pintype "passive"))
      (node (ref "R25") (pin "2") (pinfunction "2_2") (pintype "passive"))
      (node (ref "R29") (pin "2") (pinfunction "2_2") (pintype "passive"))
      (node (ref "R33") (pin "2") (pinfunction "2_2") (pintype "passive"))
      (node (ref "R37") (pin "2") (pinfunction "2_2") (pintype "passive"))
    )
    (net (code "78") (name "unconnected-(Q3-NC-Pad1)") (class "Default")
      (node (ref "Q3") (pin "1") (pinfunction "NC_1") (pintype "power_in+no_connect"))
    )
    (net (code "79") (name "unconnected-(Q3-NC-Pad4)") (class "Default")
      (node (ref "Q3") (pin "4") (pinfunction "NC_4") (pintype "power_in+no_connect"))
    )
    (net (code "80") (name "unconnected-(Q4-NC-Pad1)") (class "Default")
      (node (ref "Q4") (pin "1") (pinfunction "NC_1") (pintype "power_in+no_connect"))
    )
    (net (code "81") (name "unconnected-(Q4-NC-Pad4)") (class "Default")
      (node (ref "Q4") (pin "4") (pinfunction "NC_4") (pintype "power_in+no_connect"))
    )
    (net (code "82") (name "unconnected-(Q5-NC-Pad1)") (class "Default")
      (node (ref "Q5") (pin "1") (pinfunction "NC_1") (pintype "power_in+no_connect"))
    )
    (net (code "83") (name "unconnected-(Q5-NC-Pad4)") (class "Default")
      (node (ref "Q5") (pin "4") (pinfunction "NC_4") (pintype "power_in+no_connect"))
    )
    (net (code "84") (name "unconnected-(Q6-NC-Pad1)") (class "Default")
      (node (ref "Q6") (pin "1") (pinfunction "NC_1") (pintype "power_in+no_connect"))
    )
    (net (code "85") (name "unconnected-(Q6-NC-Pad4)") (class "Default")
      (node (ref "Q6") (pin "4") (pinfunction "NC_4") (pintype "power_in+no_connect"))
    )
    (net (code "86") (name "unconnected-(U4-JNTRST{slash}PB4-Pad40)") (class "Default")
      (node (ref "U4") (pin "40") (pinfunction "JNTRST/PB4_40") (pintype "bidirectional"))
    )
    (net (code "87") (name "unconnected-(U4-JTDO{slash}PB3-Pad39)") (class "Default")
      (node (ref "U4") (pin "39") (pinfunction "JTDO/PB3_39") (pintype "bidirectional"))
    )
    (net (code "88") (name "unconnected-(U4-PA0{slash}WKUP{slash}USART2_CTS{slash}ADC12_IN0{slash}TIM2_CH1_ETR-Pad10)") (class "Default")
      (node (ref "U4") (pin "10") (pinfunction "PA0/WKUP/USART2_CTS/ADC12_IN0/TIM2_CH1_ETR_10") (pintype "bidirectional"))
    )
    (net (code "89") (name "unconnected-(U4-PA1{slash}USART2_RTS{slash}ADC12_IN1{slash}TIM2_CH2-Pad11)") (class "Default")
      (node (ref "U4") (pin "11") (pinfunction "PA1/USART2_RTS/ADC12_IN1/TIM2_CH2_11") (pintype "bidirectional"))
    )
    (net (code "90") (name "unconnected-(U4-PA2{slash}USART2_TX{slash}ADC12_IN2{slash}TIM2_CH3-Pad12)") (class "Default")
      (node (ref "U4") (pin "12") (pinfunction "PA2/USART2_TX/ADC12_IN2/TIM2_CH3_12") (pintype "bidirectional"))
    )
    (net (code "91") (name "unconnected-(U4-PA3{slash}USART2_RX{slash}ADC12_IN3{slash}TIM2_CH4-Pad13)") (class "Default")
      (node (ref "U4") (pin "13") (pinfunction "PA3/USART2_RX/ADC12_IN3/TIM2_CH4_13") (pintype "bidirectional"))
    )
    (net (code "92") (name "unconnected-(U4-PA4{slash}SPI1_NSS{slash}USART2_CK{slash}ADC12_IN4-Pad14)") (class "Default")
      (node (ref "U4") (pin "14") (pinfunction "PA4/SPI1_NSS/USART2_CK/ADC12_IN4_14") (pintype "bidirectional"))
    )
    (net (code "93") (name "unconnected-(U4-PA5{slash}SPI1_SCK{slash}ADC12_IN5-Pad15)") (class "Default")
      (node (ref "U4") (pin "15") (pinfunction "PA5/SPI1_SCK/ADC12_IN5_15") (pintype "bidirectional"))
    )
    (net (code "94") (name "unconnected-(U4-PA6{slash}SPI1_MISO{slash}ADC12_IN6{slash}TIM3_CH1-Pad16)") (class "Default")
      (node (ref "U4") (pin "16") (pinfunction "PA6/SPI1_MISO/ADC12_IN6/TIM3_CH1_16") (pintype "bidirectional"))
    )
    (net (code "95") (name "unconnected-(U4-PA7{slash}SPI1_MOSI{slash}ADC12_IN7{slash}TIM3_CH2-Pad17)") (class "Default")
      (node (ref "U4") (pin "17") (pinfunction "PA7/SPI1_MOSI/ADC12_IN7/TIM3_CH2_17") (pintype "bidirectional"))
    )
    (net (code "96") (name "unconnected-(U4-PA11{slash}USART1_CTS{slash}CANRX{slash}TIM1_CH4{slash}USBDM-Pad32)") (class "Default")
      (node (ref "U4") (pin "32") (pinfunction "PA11/USART1_CTS/CANRX/TIM1_CH4/USBDM_32") (pintype "bidirectional"))
    )
    (net (code "97") (name "unconnected-(U4-PA12{slash}USART1_RTS{slash}CANTX{slash}TIM1_ETR{slash}USBDP-Pad33)") (class "Default")
      (node (ref "U4") (pin "33") (pinfunction "PA12/USART1_RTS/CANTX/TIM1_ETR/USBDP_33") (pintype "bidirectional"))
    )
    (net (code "98") (name "unconnected-(U4-PA15{slash}JTDI-Pad38)") (class "Default")
      (node (ref "U4") (pin "38") (pinfunction "PA15/JTDI_38") (pintype "bidirectional"))
    )
    (net (code "99") (name "unconnected-(U4-RTC{slash}TAMPER{slash}PC13-Pad2)") (class "Default")
      (node (ref "U4") (pin "2") (pinfunction "RTC/TAMPER/PC13_2") (pintype "bidirectional"))
    )
    (net (code "100") (name "unconnected-(U4-TIM3_CH3{slash}ADC12_IN8{slash}PB0-Pad18)") (class "Default")
      (node (ref "U4") (pin "18") (pinfunction "TIM3_CH3/ADC12_IN8/PB0_18") (pintype "bidirectional"))
    )
    (net (code "101") (name "unconnected-(U4-TIM3_CH4{slash}ADC12_IN9{slash}PB1-Pad19)") (class "Default")
      (node (ref "U4") (pin "19") (pinfunction "TIM3_CH4/ADC12_IN9/PB1_19") (pintype "bidirectional"))
    )
  )
)
